# psoc1_20246_A.net
KiCad netlist of a schematic drawn in EAGLE
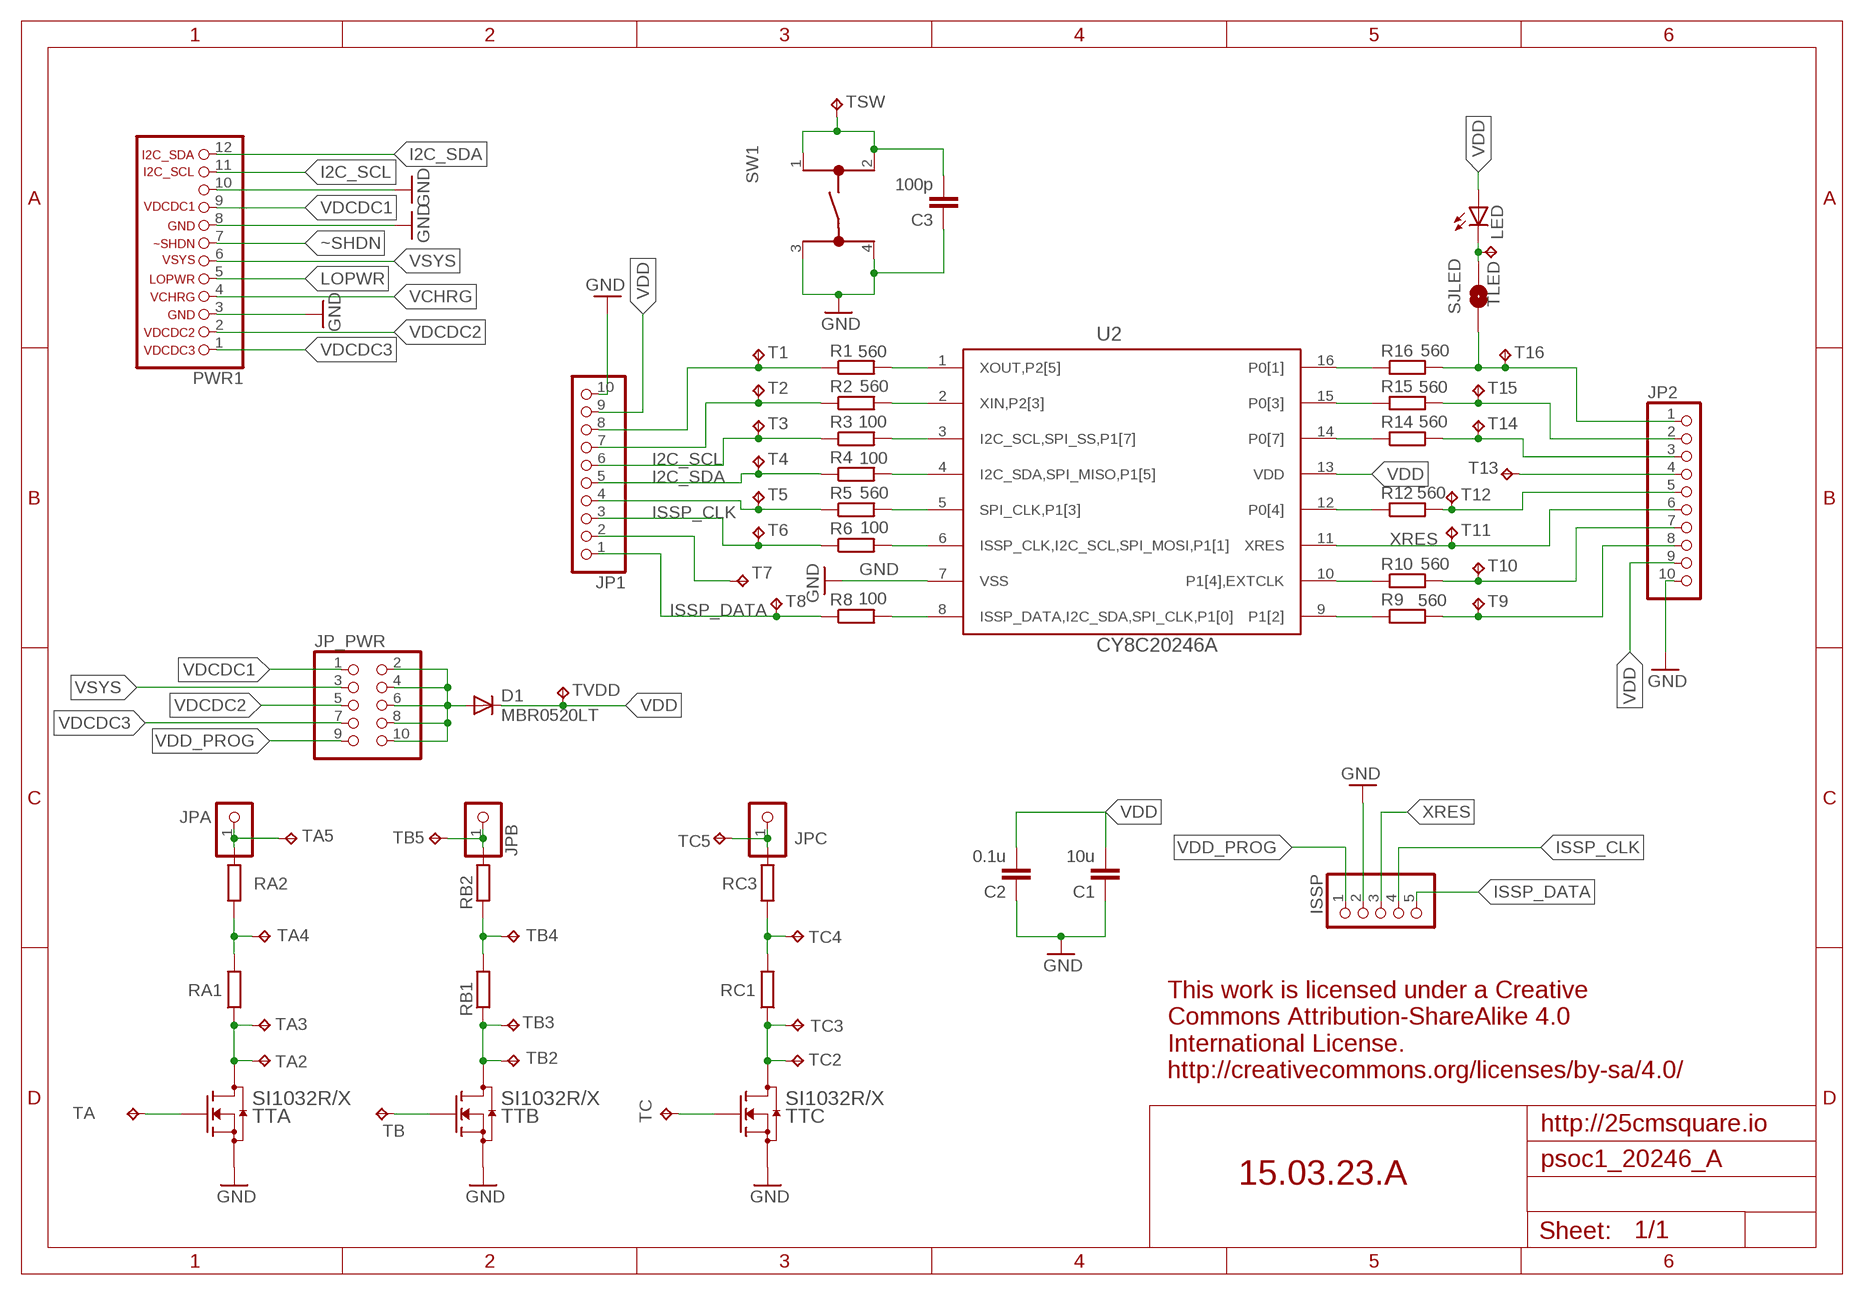
[diagram p0: schematic, sheet 1]

(export (version "E")
  (design (tool "Eeschema 10.0.6"))
  (components
    (comp (ref "C1")
      (value "10u")
      (footprint "eagle-import:C1206")
      (libsource (lib "eagle-import") (part "C-EUC1206"))
    )
    (comp (ref "C2")
      (value "0.1u")
      (footprint "eagle-import:C0603")
      (libsource (lib "eagle-import") (part "resistor_C-EUC0603"))
    )
    (comp (ref "C3")
      (value "100p")
      (footprint "eagle-import:C0603")
      (libsource (lib "eagle-import") (part "resistor_C-EUC0603"))
    )
    (comp (ref "D1")
      (value "MBR0520LT")
      (footprint "eagle-import:SOD123")
      (libsource (lib "eagle-import") (part "MBR0520LT"))
    )
    (comp (ref "ISSP")
      (value "PINHD-1X5/90")
      (footprint "eagle-import:1X05_90")
      (libsource (lib "eagle-import") (part "PINHD-1X5/90"))
    )
    (comp (ref "JP1")
      (value "PINHD-1X10")
      (footprint "eagle-import:1X10")
      (libsource (lib "eagle-import") (part "PINHD-1X10"))
    )
    (comp (ref "JP2")
      (value "PINHD-1X10")
      (footprint "eagle-import:1X10")
      (libsource (lib "eagle-import") (part "PINHD-1X10"))
    )
    (comp (ref "JPA")
      (value "PINHD-1X1")
      (footprint "eagle-import:1X01")
      (libsource (lib "eagle-import") (part "PINHD-1X1"))
    )
    (comp (ref "JPB")
      (value "PINHD-1X1")
      (footprint "eagle-import:1X01")
      (libsource (lib "eagle-import") (part "PINHD-1X1"))
    )
    (comp (ref "JPC")
      (value "PINHD-1X1")
      (footprint "eagle-import:1X01")
      (libsource (lib "eagle-import") (part "PINHD-1X1"))
    )
    (comp (ref "JP_PWR")
      (value "PINHD-2X5")
      (footprint "eagle-import:2X05")
      (libsource (lib "eagle-import") (part "PINHD-2X5"))
    )
    (comp (ref "LED")
      (value "LEDSML0603")
      (footprint "eagle-import:SML0603")
      (libsource (lib "eagle-import") (part "LEDSML0603"))
    )
    (comp (ref "PWR1")
      (value "LIWE_12_PIN_PWR")
      (footprint "eagle-import:LIWE_12_PIN")
      (libsource (lib "eagle-import") (part "LIWE_12_PIN_PWR"))
    )
    (comp (ref "R1")
      (value "560")
      (footprint "eagle-import:R0603")
      (libsource (lib "eagle-import") (part "R-EU_R0603"))
    )
    (comp (ref "R2")
      (value "560")
      (footprint "eagle-import:R0603")
      (libsource (lib "eagle-import") (part "R-EU_R0603"))
    )
    (comp (ref "R3")
      (value "100")
      (footprint "eagle-import:R0603")
      (libsource (lib "eagle-import") (part "R-EU_R0603"))
    )
    (comp (ref "R4")
      (value "100")
      (footprint "eagle-import:R0603")
      (libsource (lib "eagle-import") (part "R-EU_R0603"))
    )
    (comp (ref "R5")
      (value "560")
      (footprint "eagle-import:R0603")
      (libsource (lib "eagle-import") (part "R-EU_R0603"))
    )
    (comp (ref "R6")
      (value "100")
      (footprint "eagle-import:R0603")
      (libsource (lib "eagle-import") (part "R-EU_R0603"))
    )
    (comp (ref "R8")
      (value "100")
      (footprint "eagle-import:R0603")
      (libsource (lib "eagle-import") (part "R-EU_R0603"))
    )
    (comp (ref "R9")
      (value "560")
      (footprint "eagle-import:R0603")
      (libsource (lib "eagle-import") (part "R-EU_R0603"))
    )
    (comp (ref "R10")
      (value "560")
      (footprint "eagle-import:R0603")
      (libsource (lib "eagle-import") (part "R-EU_R0603"))
    )
    (comp (ref "R12")
      (value "560")
      (footprint "eagle-import:R0603")
      (libsource (lib "eagle-import") (part "R-EU_R0603"))
    )
    (comp (ref "R14")
      (value "560")
      (footprint "eagle-import:R0603")
      (libsource (lib "eagle-import") (part "R-EU_R0603"))
    )
    (comp (ref "R15")
      (value "560")
      (footprint "eagle-import:R0603")
      (libsource (lib "eagle-import") (part "R-EU_R0603"))
    )
    (comp (ref "R16")
      (value "560")
      (footprint "eagle-import:R0603")
      (libsource (lib "eagle-import") (part "R-EU_R0603"))
    )
    (comp (ref "RA1")
      (value "R-EU_R0603")
      (footprint "eagle-import:R0603")
      (libsource (lib "eagle-import") (part "R-EU_R0603"))
    )
    (comp (ref "RA2")
      (value "R-EU_R0603")
      (footprint "eagle-import:R0603")
      (libsource (lib "eagle-import") (part "R-EU_R0603"))
    )
    (comp (ref "RB1")
      (value "R-EU_R0603")
      (footprint "eagle-import:R0603")
      (libsource (lib "eagle-import") (part "R-EU_R0603"))
    )
    (comp (ref "RB2")
      (value "R-EU_R0603")
      (footprint "eagle-import:R0603")
      (libsource (lib "eagle-import") (part "R-EU_R0603"))
    )
    (comp (ref "RC1")
      (value "R-EU_R0603")
      (footprint "eagle-import:R0603")
      (libsource (lib "eagle-import") (part "R-EU_R0603"))
    )
    (comp (ref "RC3")
      (value "R-EU_R0603")
      (footprint "eagle-import:R0603")
      (libsource (lib "eagle-import") (part "R-EU_R0603"))
    )
    (comp (ref "SJLED")
      (value "SOLDERJUMPERNO")
      (footprint "eagle-import:SJ_2S-NO")
      (libsource (lib "eagle-import") (part "SOLDERJUMPERNO"))
    )
    (comp (ref "SW1")
      (value "FSM4JH")
      (footprint "eagle-import:FSM4JH")
      (libsource (lib "eagle-import") (part "FSM4JH"))
    )
    (comp (ref "T1")
      (value "TPTP14R")
      (footprint "eagle-import:TP14R")
      (libsource (lib "eagle-import") (part "TPTP14R"))
    )
    (comp (ref "T2")
      (value "TPTP14R")
      (footprint "eagle-import:TP14R")
      (libsource (lib "eagle-import") (part "TPTP14R"))
    )
    (comp (ref "T3")
      (value "TPTP14R")
      (footprint "eagle-import:TP14R")
      (libsource (lib "eagle-import") (part "TPTP14R"))
    )
    (comp (ref "T4")
      (value "TPTP14R")
      (footprint "eagle-import:TP14R")
      (libsource (lib "eagle-import") (part "TPTP14R"))
    )
    (comp (ref "T5")
      (value "TPTP14R")
      (footprint "eagle-import:TP14R")
      (libsource (lib "eagle-import") (part "TPTP14R"))
    )
    (comp (ref "T6")
      (value "TPTP14R")
      (footprint "eagle-import:TP14R")
      (libsource (lib "eagle-import") (part "TPTP14R"))
    )
    (comp (ref "T7")
      (value "TPTP14R")
      (footprint "eagle-import:TP14R")
      (libsource (lib "eagle-import") (part "TPTP14R"))
    )
    (comp (ref "T8")
      (value "TPTP14R")
      (footprint "eagle-import:TP14R")
      (libsource (lib "eagle-import") (part "TPTP14R"))
    )
    (comp (ref "T9")
      (value "TPTP14R")
      (footprint "eagle-import:TP14R")
      (libsource (lib "eagle-import") (part "TPTP14R"))
    )
    (comp (ref "T10")
      (value "TPTP14R")
      (footprint "eagle-import:TP14R")
      (libsource (lib "eagle-import") (part "TPTP14R"))
    )
    (comp (ref "T11")
      (value "TPTP14R")
      (footprint "eagle-import:TP14R")
      (libsource (lib "eagle-import") (part "TPTP14R"))
    )
    (comp (ref "T12")
      (value "TPTP14R")
      (footprint "eagle-import:TP14R")
      (libsource (lib "eagle-import") (part "TPTP14R"))
    )
    (comp (ref "T13")
      (value "TPTP14R")
      (footprint "eagle-import:TP14R")
      (libsource (lib "eagle-import") (part "TPTP14R"))
    )
    (comp (ref "T14")
      (value "TPTP14R")
      (footprint "eagle-import:TP14R")
      (libsource (lib "eagle-import") (part "TPTP14R"))
    )
    (comp (ref "T15")
      (value "TPTP14R")
      (footprint "eagle-import:TP14R")
      (libsource (lib "eagle-import") (part "TPTP14R"))
    )
    (comp (ref "T16")
      (value "TPTP14R")
      (footprint "eagle-import:TP14R")
      (libsource (lib "eagle-import") (part "TPTP14R"))
    )
    (comp (ref "TA")
      (value "TPTP14R")
      (footprint "eagle-import:TP14R")
      (libsource (lib "eagle-import") (part "TPTP14R"))
    )
    (comp (ref "TA2")
      (value "TPTP14R")
      (footprint "eagle-import:TP14R")
      (libsource (lib "eagle-import") (part "TPTP14R"))
    )
    (comp (ref "TA3")
      (value "TPTP14R")
      (footprint "eagle-import:TP14R")
      (libsource (lib "eagle-import") (part "TPTP14R"))
    )
    (comp (ref "TA4")
      (value "TPTP14R")
      (footprint "eagle-import:TP14R")
      (libsource (lib "eagle-import") (part "TPTP14R"))
    )
    (comp (ref "TA5")
      (value "TPTP14R")
      (footprint "eagle-import:TP14R")
      (libsource (lib "eagle-import") (part "TPTP14R"))
    )
    (comp (ref "TB")
      (value "TPTP14R")
      (footprint "eagle-import:TP14R")
      (libsource (lib "eagle-import") (part "TPTP14R"))
    )
    (comp (ref "TB2")
      (value "TPTP14R")
      (footprint "eagle-import:TP14R")
      (libsource (lib "eagle-import") (part "TPTP14R"))
    )
    (comp (ref "TB3")
      (value "TPTP14R")
      (footprint "eagle-import:TP14R")
      (libsource (lib "eagle-import") (part "TPTP14R"))
    )
    (comp (ref "TB4")
      (value "TPTP14R")
      (footprint "eagle-import:TP14R")
      (libsource (lib "eagle-import") (part "TPTP14R"))
    )
    (comp (ref "TB5")
      (value "TPTP14R")
      (footprint "eagle-import:TP14R")
      (libsource (lib "eagle-import") (part "TPTP14R"))
    )
    (comp (ref "TC")
      (value "TPTP14R")
      (footprint "eagle-import:TP14R")
      (libsource (lib "eagle-import") (part "TPTP14R"))
    )
    (comp (ref "TC2")
      (value "TPTP14R")
      (footprint "eagle-import:TP14R")
      (libsource (lib "eagle-import") (part "TPTP14R"))
    )
    (comp (ref "TC3")
      (value "TPTP14R")
      (footprint "eagle-import:TP14R")
      (libsource (lib "eagle-import") (part "TPTP14R"))
    )
    (comp (ref "TC4")
      (value "TPTP14R")
      (footprint "eagle-import:TP14R")
      (libsource (lib "eagle-import") (part "TPTP14R"))
    )
    (comp (ref "TC5")
      (value "TPTP14R")
      (footprint "eagle-import:TP14R")
      (libsource (lib "eagle-import") (part "TPTP14R"))
    )
    (comp (ref "TLED")
      (value "TPTP14R")
      (footprint "eagle-import:TP14R")
      (libsource (lib "eagle-import") (part "TPTP14R"))
    )
    (comp (ref "TSW")
      (value "TPTP14R")
      (footprint "eagle-import:TP14R")
      (libsource (lib "eagle-import") (part "TPTP14R"))
    )
    (comp (ref "TTA")
      (value "SI1032R/X")
      (footprint "eagle-import:SC-75A")
      (libsource (lib "eagle-import") (part "SI1032R/X"))
    )
    (comp (ref "TTB")
      (value "SI1032R/X")
      (footprint "eagle-import:SC-75A")
      (libsource (lib "eagle-import") (part "SI1032R/X"))
    )
    (comp (ref "TTC")
      (value "SI1032R/X")
      (footprint "eagle-import:SC-75A")
      (libsource (lib "eagle-import") (part "SI1032R/X"))
    )
    (comp (ref "TVDD")
      (value "TPTP14R")
      (footprint "eagle-import:TP14R")
      (libsource (lib "eagle-import") (part "TPTP14R"))
    )
    (comp (ref "U2")
      (value "CY8C20246A")
      (footprint "eagle-import:QFN16_3X3_NOEPAD")
      (libsource (lib "eagle-import") (part "CY8C20246A"))
    )
  )
  (nets
    (net (code "1") (name "/~{SHDN}") (class "Default")
      (node (ref "PWR1") (pin "7") (pinfunction "7_7") (pintype "passive"))
    )
    (net (code "2") (name "GND") (class "Default")
      (node (ref "C1") (pin "1") (pinfunction "1_1") (pintype "passive"))
      (node (ref "C2") (pin "1") (pinfunction "1_1") (pintype "passive"))
      (node (ref "C3") (pin "1") (pinfunction "1_1") (pintype "passive"))
      (node (ref "ISSP") (pin "2") (pinfunction "2_2") (pintype "passive"))
      (node (ref "JP1") (pin "10") (pinfunction "10_10") (pintype "passive"))
      (node (ref "JP2") (pin "10") (pinfunction "10_10") (pintype "passive"))
      (node (ref "PWR1") (pin "10") (pinfunction "10_10") (pintype "passive"))
      (node (ref "PWR1") (pin "3") (pinfunction "3_3") (pintype "passive"))
      (node (ref "PWR1") (pin "8") (pinfunction "8_8") (pintype "passive"))
      (node (ref "SW1") (pin "3") (pinfunction "3_3") (pintype "passive"))
      (node (ref "SW1") (pin "4") (pinfunction "4_4") (pintype "passive"))
      (node (ref "TTA") (pin "S") (pinfunction "S_S") (pintype "passive"))
      (node (ref "TTB") (pin "S") (pinfunction "S_S") (pintype "passive"))
      (node (ref "TTC") (pin "S") (pinfunction "S_S") (pintype "passive"))
      (node (ref "U2") (pin "7") (pinfunction "VSS_7") (pintype "power_in"))
    )
    (net (code "3") (name "I2C_SCL") (class "Default")
      (node (ref "JP1") (pin "6") (pinfunction "6_6") (pintype "passive"))
      (node (ref "PWR1") (pin "11") (pinfunction "11_11") (pintype "passive"))
      (node (ref "R3") (pin "1") (pinfunction "1_1") (pintype "passive"))
      (node (ref "T3") (pin "TP") (pinfunction "TP_TP") (pintype "input"))
    )
    (net (code "4") (name "I2C_SDA") (class "Default")
      (node (ref "JP1") (pin "5") (pinfunction "5_5") (pintype "passive"))
      (node (ref "PWR1") (pin "12") (pinfunction "12_12") (pintype "passive"))
      (node (ref "R4") (pin "1") (pinfunction "1_1") (pintype "passive"))
      (node (ref "T4") (pin "TP") (pinfunction "TP_TP") (pintype "input"))
    )
    (net (code "5") (name "ISSP_CLK") (class "Default")
      (node (ref "ISSP") (pin "4") (pinfunction "4_4") (pintype "passive"))
      (node (ref "JP1") (pin "3") (pinfunction "3_3") (pintype "passive"))
      (node (ref "R6") (pin "1") (pinfunction "1_1") (pintype "passive"))
      (node (ref "T6") (pin "TP") (pinfunction "TP_TP") (pintype "input"))
    )
    (net (code "6") (name "ISSP_DATA") (class "Default")
      (node (ref "ISSP") (pin "5") (pinfunction "5_5") (pintype "passive"))
      (node (ref "JP1") (pin "1") (pinfunction "1_1") (pintype "passive"))
      (node (ref "R8") (pin "1") (pinfunction "1_1") (pintype "passive"))
      (node (ref "T8") (pin "TP") (pinfunction "TP_TP") (pintype "input"))
    )
    (net (code "7") (name "LOPWR") (class "Default")
      (node (ref "PWR1") (pin "5") (pinfunction "5_5") (pintype "passive"))
    )
    (net (code "8") (name "Net-(C3-Pad2)") (class "Default")
      (node (ref "C3") (pin "2") (pinfunction "2_2") (pintype "passive"))
      (node (ref "SW1") (pin "1") (pinfunction "1_1") (pintype "passive"))
      (node (ref "SW1") (pin "2") (pinfunction "2_2") (pintype "passive"))
      (node (ref "TSW") (pin "TP") (pinfunction "TP_TP") (pintype "input"))
    )
    (net (code "9") (name "Net-(D1-PadA)") (class "Default")
      (node (ref "D1") (pin "A") (pinfunction "A_A") (pintype "passive"))
      (node (ref "JP_PWR") (pin "10") (pinfunction "10_10") (pintype "passive"))
      (node (ref "JP_PWR") (pin "2") (pinfunction "2_2") (pintype "passive"))
      (node (ref "JP_PWR") (pin "4") (pinfunction "4_4") (pintype "passive"))
      (node (ref "JP_PWR") (pin "6") (pinfunction "6_6") (pintype "passive"))
      (node (ref "JP_PWR") (pin "8") (pinfunction "8_8") (pintype "passive"))
    )
    (net (code "10") (name "Net-(JP1-Pad2)") (class "Default")
      (node (ref "JP1") (pin "2") (pinfunction "2_2") (pintype "passive"))
      (node (ref "T7") (pin "TP") (pinfunction "TP_TP") (pintype "input"))
    )
    (net (code "11") (name "Net-(JP1-Pad4)") (class "Default")
      (node (ref "JP1") (pin "4") (pinfunction "4_4") (pintype "passive"))
      (node (ref "R5") (pin "1") (pinfunction "1_1") (pintype "passive"))
      (node (ref "T5") (pin "TP") (pinfunction "TP_TP") (pintype "input"))
    )
    (net (code "12") (name "Net-(JP1-Pad7)") (class "Default")
      (node (ref "JP1") (pin "7") (pinfunction "7_7") (pintype "passive"))
      (node (ref "R2") (pin "1") (pinfunction "1_1") (pintype "passive"))
      (node (ref "T2") (pin "TP") (pinfunction "TP_TP") (pintype "input"))
    )
    (net (code "13") (name "Net-(JP1-Pad8)") (class "Default")
      (node (ref "JP1") (pin "8") (pinfunction "8_8") (pintype "passive"))
      (node (ref "R1") (pin "1") (pinfunction "1_1") (pintype "passive"))
      (node (ref "T1") (pin "TP") (pinfunction "TP_TP") (pintype "input"))
    )
    (net (code "14") (name "Net-(JP2-Pad1)") (class "Default")
      (node (ref "JP2") (pin "1") (pinfunction "1_1") (pintype "passive"))
      (node (ref "R16") (pin "2") (pinfunction "2_2") (pintype "passive"))
      (node (ref "SJLED") (pin "1") (pinfunction "1_1") (pintype "passive"))
      (node (ref "T16") (pin "TP") (pinfunction "TP_TP") (pintype "input"))
    )
    (net (code "15") (name "Net-(JP2-Pad2)") (class "Default")
      (node (ref "JP2") (pin "2") (pinfunction "2_2") (pintype "passive"))
      (node (ref "R15") (pin "2") (pinfunction "2_2") (pintype "passive"))
      (node (ref "T15") (pin "TP") (pinfunction "TP_TP") (pintype "input"))
    )
    (net (code "16") (name "Net-(JP2-Pad3)") (class "Default")
      (node (ref "JP2") (pin "3") (pinfunction "3_3") (pintype "passive"))
      (node (ref "R14") (pin "2") (pinfunction "2_2") (pintype "passive"))
      (node (ref "T14") (pin "TP") (pinfunction "TP_TP") (pintype "input"))
    )
    (net (code "17") (name "Net-(JP2-Pad4)") (class "Default")
      (node (ref "JP2") (pin "4") (pinfunction "4_4") (pintype "passive"))
      (node (ref "T13") (pin "TP") (pinfunction "TP_TP") (pintype "input"))
    )
    (net (code "18") (name "Net-(JP2-Pad5)") (class "Default")
      (node (ref "JP2") (pin "5") (pinfunction "5_5") (pintype "passive"))
      (node (ref "R12") (pin "2") (pinfunction "2_2") (pintype "passive"))
      (node (ref "T12") (pin "TP") (pinfunction "TP_TP") (pintype "input"))
    )
    (net (code "19") (name "Net-(JP2-Pad7)") (class "Default")
      (node (ref "JP2") (pin "7") (pinfunction "7_7") (pintype "passive"))
      (node (ref "R10") (pin "2") (pinfunction "2_2") (pintype "passive"))
      (node (ref "T10") (pin "TP") (pinfunction "TP_TP") (pintype "input"))
    )
    (net (code "20") (name "Net-(JP2-Pad8)") (class "Default")
      (node (ref "JP2") (pin "8") (pinfunction "8_8") (pintype "passive"))
      (node (ref "R9") (pin "2") (pinfunction "2_2") (pintype "passive"))
      (node (ref "T9") (pin "TP") (pinfunction "TP_TP") (pintype "input"))
    )
    (net (code "21") (name "Net-(JPA-Pad1)") (class "Default")
      (node (ref "JPA") (pin "1") (pinfunction "1_1") (pintype "passive"))
      (node (ref "RA2") (pin "2") (pinfunction "2_2") (pintype "passive"))
      (node (ref "TA5") (pin "TP") (pinfunction "TP_TP") (pintype "input"))
    )
    (net (code "22") (name "Net-(JPB-Pad1)") (class "Default")
      (node (ref "JPB") (pin "1") (pinfunction "1_1") (pintype "passive"))
      (node (ref "RB2") (pin "2") (pinfunction "2_2") (pintype "passive"))
      (node (ref "TB5") (pin "TP") (pinfunction "TP_TP") (pintype "input"))
    )
    (net (code "23") (name "Net-(JPC-Pad1)") (class "Default")
      (node (ref "JPC") (pin "1") (pinfunction "1_1") (pintype "passive"))
      (node (ref "RC3") (pin "2") (pinfunction "2_2") (pintype "passive"))
      (node (ref "TC5") (pin "TP") (pinfunction "TP_TP") (pintype "input"))
    )
    (net (code "24") (name "Net-(LED-PadC)") (class "Default")
      (node (ref "LED") (pin "C") (pinfunction "C_C") (pintype "passive"))
      (node (ref "SJLED") (pin "2") (pinfunction "2_2") (pintype "passive"))
      (node (ref "TLED") (pin "TP") (pinfunction "TP_TP") (pintype "input"))
    )
    (net (code "25") (name "Net-(RA1-Pad1)") (class "Default")
      (node (ref "RA1") (pin "1") (pinfunction "1_1") (pintype "passive"))
      (node (ref "TA2") (pin "TP") (pinfunction "TP_TP") (pintype "input"))
      (node (ref "TA3") (pin "TP") (pinfunction "TP_TP") (pintype "input"))
      (node (ref "TTA") (pin "D") (pinfunction "D_D") (pintype "passive"))
    )
    (net (code "26") (name "Net-(RA1-Pad2)") (class "Default")
      (node (ref "RA1") (pin "2") (pinfunction "2_2") (pintype "passive"))
      (node (ref "RA2") (pin "1") (pinfunction "1_1") (pintype "passive"))
      (node (ref "TA4") (pin "TP") (pinfunction "TP_TP") (pintype "input"))
    )
    (net (code "27") (name "Net-(RB1-Pad1)") (class "Default")
      (node (ref "RB1") (pin "1") (pinfunction "1_1") (pintype "passive"))
      (node (ref "TB2") (pin "TP") (pinfunction "TP_TP") (pintype "input"))
      (node (ref "TB3") (pin "TP") (pinfunction "TP_TP") (pintype "input"))
      (node (ref "TTB") (pin "D") (pinfunction "D_D") (pintype "passive"))
    )
    (net (code "28") (name "Net-(RB1-Pad2)") (class "Default")
      (node (ref "RB1") (pin "2") (pinfunction "2_2") (pintype "passive"))
      (node (ref "RB2") (pin "1") (pinfunction "1_1") (pintype "passive"))
      (node (ref "TB4") (pin "TP") (pinfunction "TP_TP") (pintype "input"))
    )
    (net (code "29") (name "Net-(RC1-Pad1)") (class "Default")
      (node (ref "RC1") (pin "1") (pinfunction "1_1") (pintype "passive"))
      (node (ref "TC2") (pin "TP") (pinfunction "TP_TP") (pintype "input"))
      (node (ref "TC3") (pin "TP") (pinfunction "TP_TP") (pintype "input"))
      (node (ref "TTC") (pin "D") (pinfunction "D_D") (pintype "passive"))
    )
    (net (code "30") (name "Net-(RC1-Pad2)") (class "Default")
      (node (ref "RC1") (pin "2") (pinfunction "2_2") (pintype "passive"))
      (node (ref "RC3") (pin "1") (pinfunction "1_1") (pintype "passive"))
      (node (ref "TC4") (pin "TP") (pinfunction "TP_TP") (pintype "input"))
    )
    (net (code "31") (name "Net-(TA-PadTP)") (class "Default")
      (node (ref "TA") (pin "TP") (pinfunction "TP_TP") (pintype "input"))
      (node (ref "TTA") (pin "G") (pinfunction "G_G") (pintype "passive"))
    )
    (net (code "32") (name "Net-(TB-PadTP)") (class "Default")
      (node (ref "TB") (pin "TP") (pinfunction "TP_TP") (pintype "input"))
      (node (ref "TTB") (pin "G") (pinfunction "G_G") (pintype "passive"))
    )
    (net (code "33") (name "Net-(TC-PadTP)") (class "Default")
      (node (ref "TC") (pin "TP") (pinfunction "TP_TP") (pintype "input"))
      (node (ref "TTC") (pin "G") (pinfunction "G_G") (pintype "passive"))
    )
    (net (code "34") (name "Net-(U2-I2C_SCL,SPI_SS,P1[7])") (class "Default")
      (node (ref "R3") (pin "2") (pinfunction "2_2") (pintype "passive"))
      (node (ref "U2") (pin "3") (pinfunction "I2C_SCL,SPI_SS,P1[7]_3") (pintype "bidirectional"))
    )
    (net (code "35") (name "Net-(U2-I2C_SDA,SPI_MISO,P1[5])") (class "Default")
      (node (ref "R4") (pin "2") (pinfunction "2_2") (pintype "passive"))
      (node (ref "U2") (pin "4") (pinfunction "I2C_SDA,SPI_MISO,P1[5]_4") (pintype "bidirectional"))
    )
    (net (code "36") (name "Net-(U2-ISSP_CLK,I2C_SCL,SPI_MOSI,P1[1])") (class "Default")
      (node (ref "R6") (pin "2") (pinfunction "2_2") (pintype "passive"))
      (node (ref "U2") (pin "6") (pinfunction "ISSP_CLK,I2C_SCL,SPI_MOSI,P1[1]_6") (pintype "bidirectional"))
    )
    (net (code "37") (name "Net-(U2-ISSP_DATA,I2C_SDA,SPI_CLK,P1[0])") (class "Default")
      (node (ref "R8") (pin "2") (pinfunction "2_2") (pintype "passive"))
      (node (ref "U2") (pin "8") (pinfunction "ISSP_DATA,I2C_SDA,SPI_CLK,P1[0]_8") (pintype "bidirectional"))
    )
    (net (code "38") (name "Net-(U2-P0[1])") (class "Default")
      (node (ref "R16") (pin "1") (pinfunction "1_1") (pintype "passive"))
      (node (ref "U2") (pin "16") (pinfunction "P0[1]_16") (pintype "bidirectional"))
    )
    (net (code "39") (name "Net-(U2-P0[3])") (class "Default")
      (node (ref "R15") (pin "1") (pinfunction "1_1") (pintype "passive"))
      (node (ref "U2") (pin "15") (pinfunction "P0[3]_15") (pintype "bidirectional"))
    )
    (net (code "40") (name "Net-(U2-P0[4])") (class "Default")
      (node (ref "R12") (pin "1") (pinfunction "1_1") (pintype "passive"))
      (node (ref "U2") (pin "12") (pinfunction "P0[4]_12") (pintype "bidirectional"))
    )
    (net (code "41") (name "Net-(U2-P0[7])") (class "Default")
      (node (ref "R14") (pin "1") (pinfunction "1_1") (pintype "passive"))
      (node (ref "U2") (pin "14") (pinfunction "P0[7]_14") (pintype "bidirectional"))
    )
    (net (code "42") (name "Net-(U2-P1[2])") (class "Default")
      (node (ref "R9") (pin "1") (pinfunction "1_1") (pintype "passive"))
      (node (ref "U2") (pin "9") (pinfunction "P1[2]_9") (pintype "bidirectional"))
    )
    (net (code "43") (name "Net-(U2-P1[4],EXTCLK)") (class "Default")
      (node (ref "R10") (pin "1") (pinfunction "1_1") (pintype "passive"))
      (node (ref "U2") (pin "10") (pinfunction "P1[4],EXTCLK_10") (pintype "bidirectional"))
    )
    (net (code "44") (name "Net-(U2-SPI_CLK,P1[3])") (class "Default")
      (node (ref "R5") (pin "2") (pinfunction "2_2") (pintype "passive"))
      (node (ref "U2") (pin "5") (pinfunction "SPI_CLK,P1[3]_5") (pintype "bidirectional"))
    )
    (net (code "45") (name "Net-(U2-XIN,P2[3])") (class "Default")
      (node (ref "R2") (pin "2") (pinfunction "2_2") (pintype "passive"))
      (node (ref "U2") (pin "2") (pinfunction "XIN,P2[3]_2") (pintype "bidirectional"))
    )
    (net (code "46") (name "Net-(U2-XOUT,P2[5])") (class "Default")
      (node (ref "R1") (pin "2") (pinfunction "2_2") (pintype "passive"))
      (node (ref "U2") (pin "1") (pinfunction "XOUT,P2[5]_1") (pintype "bidirectional"))
    )
    (net (code "47") (name "VCHRG") (class "Default")
      (node (ref "PWR1") (pin "4") (pinfunction "4_4") (pintype "passive"))
    )
    (net (code "48") (name "VDCDC1") (class "Default")
      (node (ref "JP_PWR") (pin "1") (pinfunction "1_1") (pintype "passive"))
      (node (ref "PWR1") (pin "9") (pinfunction "9_9") (pintype "passive"))
    )
    (net (code "49") (name "VDCDC2") (class "Default")
      (node (ref "JP_PWR") (pin "5") (pinfunction "5_5") (pintype "passive"))
      (node (ref "PWR1") (pin "2") (pinfunction "2_2") (pintype "passive"))
    )
    (net (code "50") (name "VDCDC3") (class "Default")
      (node (ref "JP_PWR") (pin "7") (pinfunction "7_7") (pintype "passive"))
      (node (ref "PWR1") (pin "1") (pinfunction "1_1") (pintype "passive"))
    )
    (net (code "51") (name "VDD") (class "Default")
      (node (ref "C1") (pin "2") (pinfunction "2_2") (pintype "passive"))
      (node (ref "C2") (pin "2") (pinfunction "2_2") (pintype "passive"))
      (node (ref "D1") (pin "C") (pinfunction "C_C") (pintype "passive"))
      (node (ref "JP1") (pin "9") (pinfunction "9_9") (pintype "passive"))
      (node (ref "JP2") (pin "9") (pinfunction "9_9") (pintype "passive"))
      (node (ref "LED") (pin "A") (pinfunction "A_A") (pintype "passive"))
      (node (ref "TVDD") (pin "TP") (pinfunction "TP_TP") (pintype "input"))
      (node (ref "U2") (pin "13") (pinfunction "VDD_13") (pintype "power_in"))
    )
    (net (code "52") (name "VDD_PROG") (class "Default")
      (node (ref "ISSP") (pin "1") (pinfunction "1_1") (pintype "passive"))
      (node (ref "JP_PWR") (pin "9") (pinfunction "9_9") (pintype "passive"))
    )
    (net (code "53") (name "VSYS") (class "Default")
      (node (ref "JP_PWR") (pin "3") (pinfunction "3_3") (pintype "passive"))
      (node (ref "PWR1") (pin "6") (pinfunction "6_6") (pintype "passive"))
    )
    (net (code "54") (name "XRES") (class "Default")
      (node (ref "ISSP") (pin "3") (pinfunction "3_3") (pintype "passive"))
      (node (ref "JP2") (pin "6") (pinfunction "6_6") (pintype "passive"))
      (node (ref "T11") (pin "TP") (pinfunction "TP_TP") (pintype "input"))
      (node (ref "U2") (pin "11") (pinfunction "XRES_11") (pintype "bidirectional"))
    )
  )
)
